# 16-Bit_Register.net
KiCad netlist of a schematic drawn in EAGLE
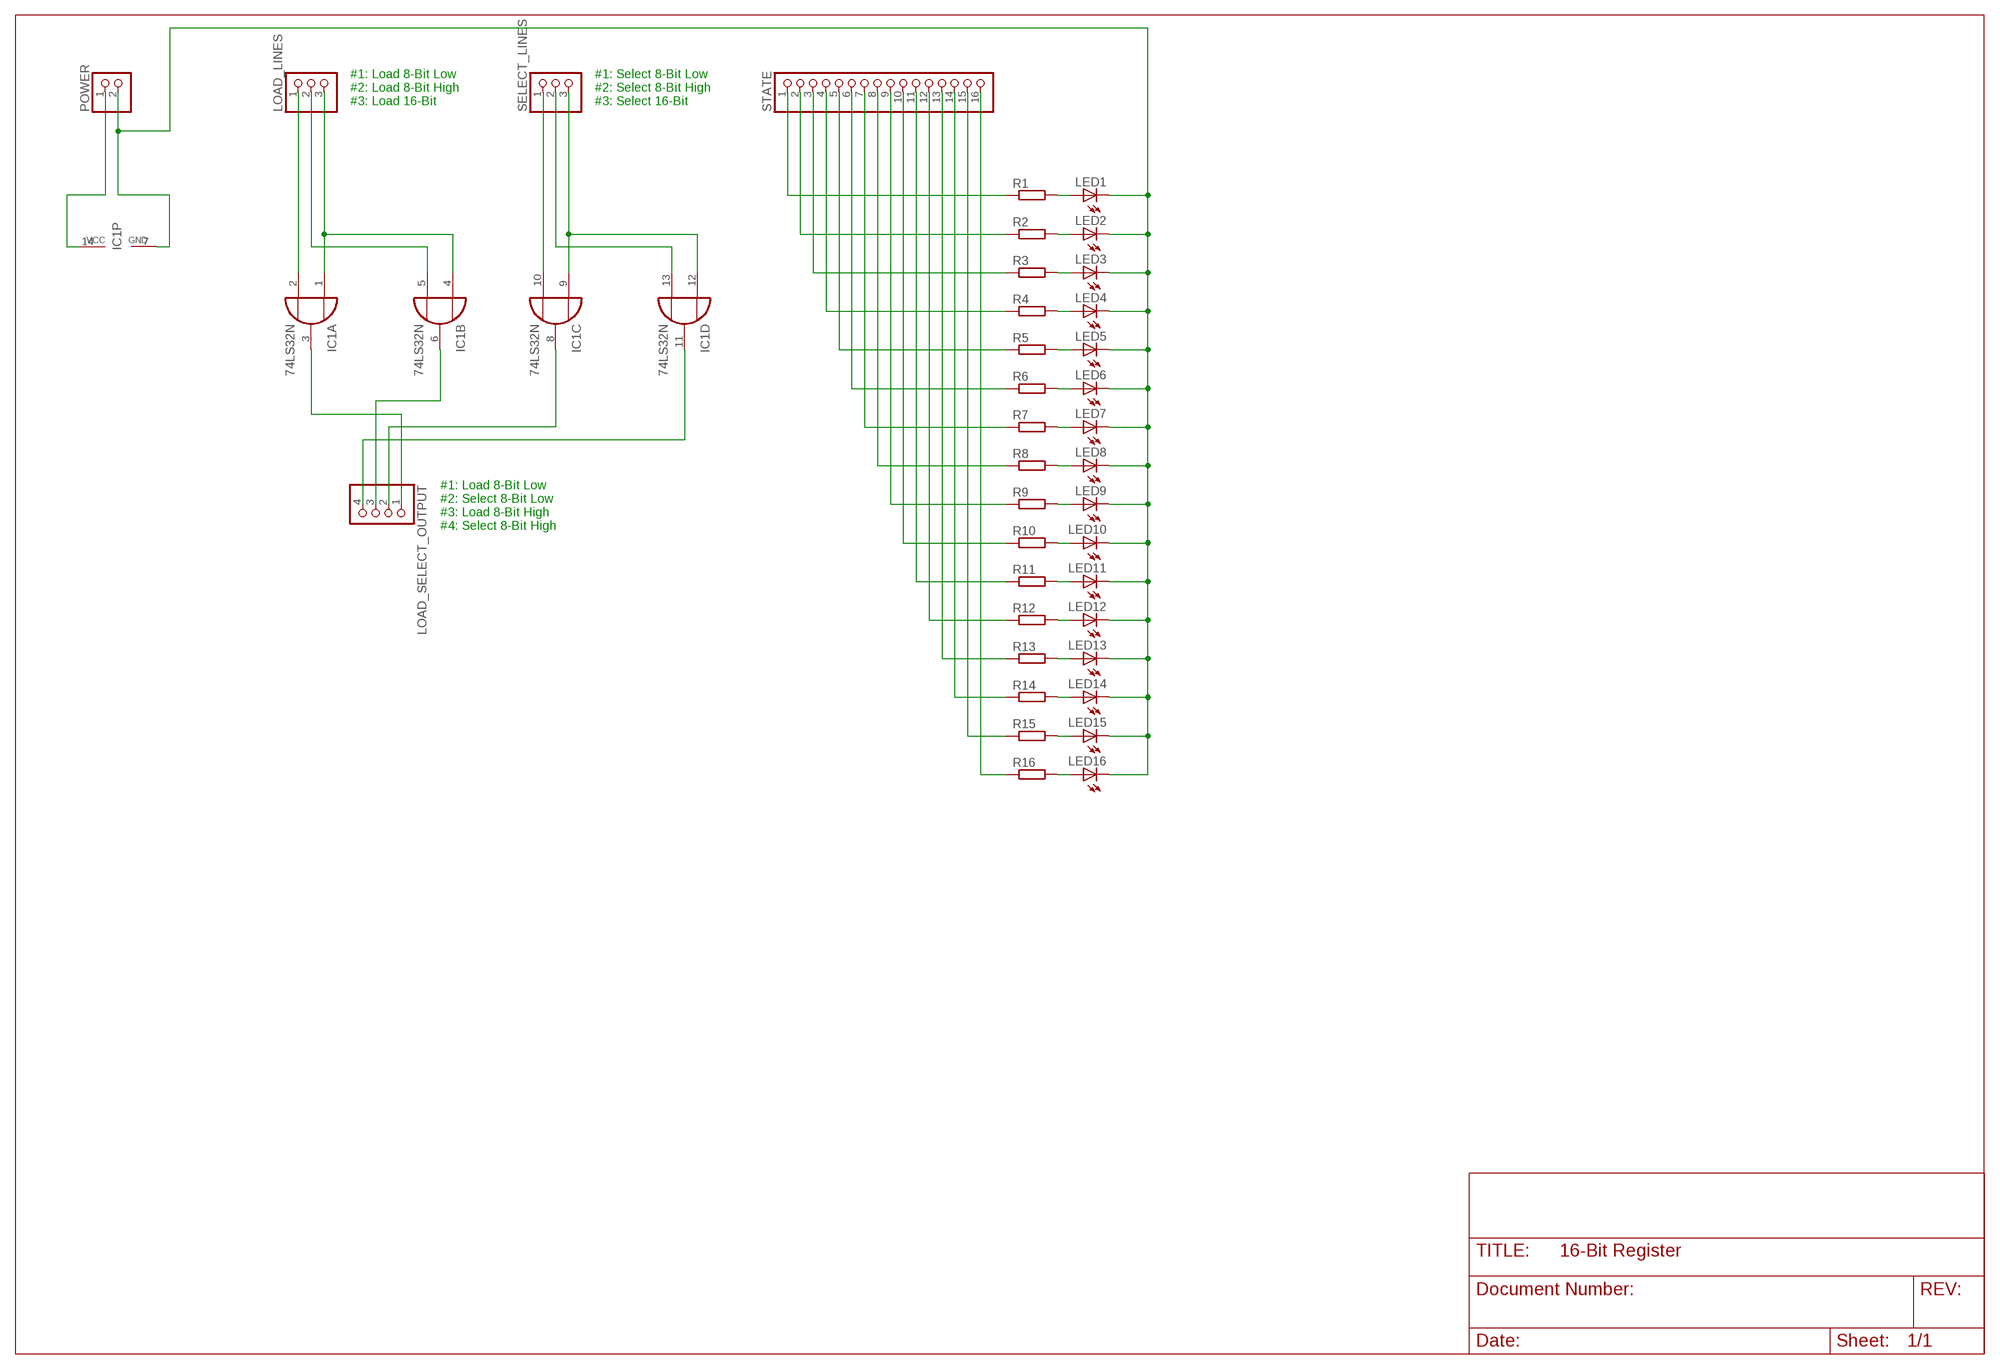
[diagram p0: schematic, sheet 1]

(export (version "E")
  (design (tool "Eeschema 10.0.6"))
  (components
    (comp (ref "IC1")
      (value "74LS32N")
      (footprint "eagle-import:DIL14")
      (libsource (lib "eagle-import") (part "7432NLS"))
    )
    (comp (ref "LED1")
      (value "LED3MM")
      (footprint "eagle-import:LED3MM")
      (libsource (lib "eagle-import") (part "LED3MM"))
    )
    (comp (ref "LED2")
      (value "LED3MM")
      (footprint "eagle-import:LED3MM")
      (libsource (lib "eagle-import") (part "LED3MM"))
    )
    (comp (ref "LED3")
      (value "LED3MM")
      (footprint "eagle-import:LED3MM")
      (libsource (lib "eagle-import") (part "LED3MM"))
    )
    (comp (ref "LED4")
      (value "LED3MM")
      (footprint "eagle-import:LED3MM")
      (libsource (lib "eagle-import") (part "LED3MM"))
    )
    (comp (ref "LED5")
      (value "LED3MM")
      (footprint "eagle-import:LED3MM")
      (libsource (lib "eagle-import") (part "LED3MM"))
    )
    (comp (ref "LED6")
      (value "LED3MM")
      (footprint "eagle-import:LED3MM")
      (libsource (lib "eagle-import") (part "LED3MM"))
    )
    (comp (ref "LED7")
      (value "LED3MM")
      (footprint "eagle-import:LED3MM")
      (libsource (lib "eagle-import") (part "LED3MM"))
    )
    (comp (ref "LED8")
      (value "LED3MM")
      (footprint "eagle-import:LED3MM")
      (libsource (lib "eagle-import") (part "LED3MM"))
    )
    (comp (ref "LED9")
      (value "LED3MM")
      (footprint "eagle-import:LED3MM")
      (libsource (lib "eagle-import") (part "LED3MM"))
    )
    (comp (ref "LED10")
      (value "LED3MM")
      (footprint "eagle-import:LED3MM")
      (libsource (lib "eagle-import") (part "LED3MM"))
    )
    (comp (ref "LED11")
      (value "LED3MM")
      (footprint "eagle-import:LED3MM")
      (libsource (lib "eagle-import") (part "LED3MM"))
    )
    (comp (ref "LED12")
      (value "LED3MM")
      (footprint "eagle-import:LED3MM")
      (libsource (lib "eagle-import") (part "LED3MM"))
    )
    (comp (ref "LED13")
      (value "LED3MM")
      (footprint "eagle-import:LED3MM")
      (libsource (lib "eagle-import") (part "LED3MM"))
    )
    (comp (ref "LED14")
      (value "LED3MM")
      (footprint "eagle-import:LED3MM")
      (libsource (lib "eagle-import") (part "LED3MM"))
    )
    (comp (ref "LED15")
      (value "LED3MM")
      (footprint "eagle-import:LED3MM")
      (libsource (lib "eagle-import") (part "LED3MM"))
    )
    (comp (ref "LED16")
      (value "LED3MM")
      (footprint "eagle-import:LED3MM")
      (libsource (lib "eagle-import") (part "LED3MM"))
    )
    (comp (ref "LOAD_LINES")
      (value "PINHD-1X3")
      (footprint "eagle-import:1X03")
      (libsource (lib "eagle-import") (part "PINHD-1X3"))
    )
    (comp (ref "LOAD_SELECT_OUTPUT")
      (value "PINHD-1X4")
      (footprint "eagle-import:1X04")
      (libsource (lib "eagle-import") (part "PINHD-1X4"))
    )
    (comp (ref "POWER")
      (value "PINHD-1X2")
      (footprint "eagle-import:1X02")
      (libsource (lib "eagle-import") (part "PINHD-1X2"))
    )
    (comp (ref "R1")
      (value "R-EU_0207/7")
      (footprint "eagle-import:0207_7")
      (libsource (lib "eagle-import") (part "R-EU_0207/7"))
    )
    (comp (ref "R2")
      (value "R-EU_0207/7")
      (footprint "eagle-import:0207_7")
      (libsource (lib "eagle-import") (part "R-EU_0207/7"))
    )
    (comp (ref "R3")
      (value "R-EU_0207/7")
      (footprint "eagle-import:0207_7")
      (libsource (lib "eagle-import") (part "R-EU_0207/7"))
    )
    (comp (ref "R4")
      (value "R-EU_0207/7")
      (footprint "eagle-import:0207_7")
      (libsource (lib "eagle-import") (part "R-EU_0207/7"))
    )
    (comp (ref "R5")
      (value "R-EU_0207/7")
      (footprint "eagle-import:0207_7")
      (libsource (lib "eagle-import") (part "R-EU_0207/7"))
    )
    (comp (ref "R6")
      (value "R-EU_0207/7")
      (footprint "eagle-import:0207_7")
      (libsource (lib "eagle-import") (part "R-EU_0207/7"))
    )
    (comp (ref "R7")
      (value "R-EU_0207/7")
      (footprint "eagle-import:0207_7")
      (libsource (lib "eagle-import") (part "R-EU_0207/7"))
    )
    (comp (ref "R8")
      (value "R-EU_0207/7")
      (footprint "eagle-import:0207_7")
      (libsource (lib "eagle-import") (part "R-EU_0207/7"))
    )
    (comp (ref "R9")
      (value "R-EU_0207/7")
      (footprint "eagle-import:0207_7")
      (libsource (lib "eagle-import") (part "R-EU_0207/7"))
    )
    (comp (ref "R10")
      (value "R-EU_0207/7")
      (footprint "eagle-import:0207_7")
      (libsource (lib "eagle-import") (part "R-EU_0207/7"))
    )
    (comp (ref "R11")
      (value "R-EU_0207/7")
      (footprint "eagle-import:0207_7")
      (libsource (lib "eagle-import") (part "R-EU_0207/7"))
    )
    (comp (ref "R12")
      (value "R-EU_0207/7")
      (footprint "eagle-import:0207_7")
      (libsource (lib "eagle-import") (part "R-EU_0207/7"))
    )
    (comp (ref "R13")
      (value "R-EU_0207/7")
      (footprint "eagle-import:0207_7")
      (libsource (lib "eagle-import") (part "R-EU_0207/7"))
    )
    (comp (ref "R14")
      (value "R-EU_0207/7")
      (footprint "eagle-import:0207_7")
      (libsource (lib "eagle-import") (part "R-EU_0207/7"))
    )
    (comp (ref "R15")
      (value "R-EU_0207/7")
      (footprint "eagle-import:0207_7")
      (libsource (lib "eagle-import") (part "R-EU_0207/7"))
    )
    (comp (ref "R16")
      (value "R-EU_0207/7")
      (footprint "eagle-import:0207_7")
      (libsource (lib "eagle-import") (part "R-EU_0207/7"))
    )
    (comp (ref "SELECT_LINES")
      (value "PINHD-1X3")
      (footprint "eagle-import:1X03")
      (libsource (lib "eagle-import") (part "PINHD-1X3"))
    )
    (comp (ref "STATE")
      (value "PINHD-1X16")
      (footprint "eagle-import:1X16")
      (libsource (lib "eagle-import") (part "PINHD-1X16"))
    )
  )
  (nets
    (net (code "1") (name "Net-(IC1A-I0)") (class "Default")
      (node (ref "IC1") (pin "1") (pinfunction "I0_1") (pintype "input"))
      (node (ref "IC1") (pin "4") (pinfunction "I0_4") (pintype "input"))
      (node (ref "LOAD_LINES") (pin "3") (pinfunction "3_3") (pintype "passive"))
    )
    (net (code "2") (name "Net-(IC1A-I1)") (class "Default")
      (node (ref "IC1") (pin "2") (pinfunction "I1_2") (pintype "input"))
      (node (ref "LOAD_LINES") (pin "1") (pinfunction "1_1") (pintype "passive"))
    )
    (net (code "3") (name "Net-(IC1A-O)") (class "Default")
      (node (ref "IC1") (pin "3") (pinfunction "O_3") (pintype "output"))
      (node (ref "LOAD_SELECT_OUTPUT") (pin "1") (pinfunction "1_1") (pintype "passive"))
    )
    (net (code "4") (name "Net-(IC1B-I1)") (class "Default")
      (node (ref "IC1") (pin "5") (pinfunction "I1_5") (pintype "input"))
      (node (ref "LOAD_LINES") (pin "2") (pinfunction "2_2") (pintype "passive"))
    )
    (net (code "5") (name "Net-(IC1B-O)") (class "Default")
      (node (ref "IC1") (pin "6") (pinfunction "O_6") (pintype "output"))
      (node (ref "LOAD_SELECT_OUTPUT") (pin "3") (pinfunction "3_3") (pintype "passive"))
    )
    (net (code "6") (name "Net-(IC1C-I0)") (class "Default")
      (node (ref "IC1") (pin "12") (pinfunction "I0_12") (pintype "input"))
      (node (ref "IC1") (pin "9") (pinfunction "I0_9") (pintype "input"))
      (node (ref "SELECT_LINES") (pin "3") (pinfunction "3_3") (pintype "passive"))
    )
    (net (code "7") (name "Net-(IC1C-I1)") (class "Default")
      (node (ref "IC1") (pin "10") (pinfunction "I1_10") (pintype "input"))
      (node (ref "SELECT_LINES") (pin "1") (pinfunction "1_1") (pintype "passive"))
    )
    (net (code "8") (name "Net-(IC1C-O)") (class "Default")
      (node (ref "IC1") (pin "8") (pinfunction "O_8") (pintype "output"))
      (node (ref "LOAD_SELECT_OUTPUT") (pin "2") (pinfunction "2_2") (pintype "passive"))
    )
    (net (code "9") (name "Net-(IC1D-I1)") (class "Default")
      (node (ref "IC1") (pin "13") (pinfunction "I1_13") (pintype "input"))
      (node (ref "SELECT_LINES") (pin "2") (pinfunction "2_2") (pintype "passive"))
    )
    (net (code "10") (name "Net-(IC1D-O)") (class "Default")
      (node (ref "IC1") (pin "11") (pinfunction "O_11") (pintype "output"))
      (node (ref "LOAD_SELECT_OUTPUT") (pin "4") (pinfunction "4_4") (pintype "passive"))
    )
    (net (code "11") (name "Net-(IC1E-GND)") (class "Default")
      (node (ref "IC1") (pin "7") (pinfunction "GND_7") (pintype "power_in"))
      (node (ref "LED1") (pin "K") (pinfunction "C_K") (pintype "passive"))
      (node (ref "LED10") (pin "K") (pinfunction "C_K") (pintype "passive"))
      (node (ref "LED11") (pin "K") (pinfunction "C_K") (pintype "passive"))
      (node (ref "LED12") (pin "K") (pinfunction "C_K") (pintype "passive"))
      (node (ref "LED13") (pin "K") (pinfunction "C_K") (pintype "passive"))
      (node (ref "LED14") (pin "K") (pinfunction "C_K") (pintype "passive"))
      (node (ref "LED15") (pin "K") (pinfunction "C_K") (pintype "passive"))
      (node (ref "LED16") (pin "K") (pinfunction "C_K") (pintype "passive"))
      (node (ref "LED2") (pin "K") (pinfunction "C_K") (pintype "passive"))
      (node (ref "LED3") (pin "K") (pinfunction "C_K") (pintype "passive"))
      (node (ref "LED4") (pin "K") (pinfunction "C_K") (pintype "passive"))
      (node (ref "LED5") (pin "K") (pinfunction "C_K") (pintype "passive"))
      (node (ref "LED6") (pin "K") (pinfunction "C_K") (pintype "passive"))
      (node (ref "LED7") (pin "K") (pinfunction "C_K") (pintype "passive"))
      (node (ref "LED8") (pin "K") (pinfunction "C_K") (pintype "passive"))
      (node (ref "LED9") (pin "K") (pinfunction "C_K") (pintype "passive"))
      (node (ref "POWER") (pin "2") (pinfunction "2_2") (pintype "passive"))
    )
    (net (code "12") (name "Net-(IC1E-VCC)") (class "Default")
      (node (ref "IC1") (pin "14") (pinfunction "VCC_14") (pintype "power_in"))
      (node (ref "POWER") (pin "1") (pinfunction "1_1") (pintype "passive"))
    )
    (net (code "13") (name "Net-(LED1-PadA)") (class "Default")
      (node (ref "LED1") (pin "A") (pinfunction "A_A") (pintype "passive"))
      (node (ref "R1") (pin "2") (pinfunction "2_2") (pintype "passive"))
    )
    (net (code "14") (name "Net-(LED2-PadA)") (class "Default")
      (node (ref "LED2") (pin "A") (pinfunction "A_A") (pintype "passive"))
      (node (ref "R2") (pin "2") (pinfunction "2_2") (pintype "passive"))
    )
    (net (code "15") (name "Net-(LED3-PadA)") (class "Default")
      (node (ref "LED3") (pin "A") (pinfunction "A_A") (pintype "passive"))
      (node (ref "R3") (pin "2") (pinfunction "2_2") (pintype "passive"))
    )
    (net (code "16") (name "Net-(LED4-PadA)") (class "Default")
      (node (ref "LED4") (pin "A") (pinfunction "A_A") (pintype "passive"))
      (node (ref "R4") (pin "2") (pinfunction "2_2") (pintype "passive"))
    )
    (net (code "17") (name "Net-(LED5-PadA)") (class "Default")
      (node (ref "LED5") (pin "A") (pinfunction "A_A") (pintype "passive"))
      (node (ref "R5") (pin "2") (pinfunction "2_2") (pintype "passive"))
    )
    (net (code "18") (name "Net-(LED6-PadA)") (class "Default")
      (node (ref "LED6") (pin "A") (pinfunction "A_A") (pintype "passive"))
      (node (ref "R6") (pin "2") (pinfunction "2_2") (pintype "passive"))
    )
    (net (code "19") (name "Net-(LED7-PadA)") (class "Default")
      (node (ref "LED7") (pin "A") (pinfunction "A_A") (pintype "passive"))
      (node (ref "R7") (pin "2") (pinfunction "2_2") (pintype "passive"))
    )
    (net (code "20") (name "Net-(LED8-PadA)") (class "Default")
      (node (ref "LED8") (pin "A") (pinfunction "A_A") (pintype "passive"))
      (node (ref "R8") (pin "2") (pinfunction "2_2") (pintype "passive"))
    )
    (net (code "21") (name "Net-(LED9-PadA)") (class "Default")
      (node (ref "LED9") (pin "A") (pinfunction "A_A") (pintype "passive"))
      (node (ref "R9") (pin "2") (pinfunction "2_2") (pintype "passive"))
    )
    (net (code "22") (name "Net-(LED10-PadA)") (class "Default")
      (node (ref "LED10") (pin "A") (pinfunction "A_A") (pintype "passive"))
      (node (ref "R10") (pin "2") (pinfunction "2_2") (pintype "passive"))
    )
    (net (code "23") (name "Net-(LED11-PadA)") (class "Default")
      (node (ref "LED11") (pin "A") (pinfunction "A_A") (pintype "passive"))
      (node (ref "R11") (pin "2") (pinfunction "2_2") (pintype "passive"))
    )
    (net (code "24") (name "Net-(LED12-PadA)") (class "Default")
      (node (ref "LED12") (pin "A") (pinfunction "A_A") (pintype "passive"))
      (node (ref "R12") (pin "2") (pinfunction "2_2") (pintype "passive"))
    )
    (net (code "25") (name "Net-(LED13-PadA)") (class "Default")
      (node (ref "LED13") (pin "A") (pinfunction "A_A") (pintype "passive"))
      (node (ref "R13") (pin "2") (pinfunction "2_2") (pintype "passive"))
    )
    (net (code "26") (name "Net-(LED14-PadA)") (class "Default")
      (node (ref "LED14") (pin "A") (pinfunction "A_A") (pintype "passive"))
      (node (ref "R14") (pin "2") (pinfunction "2_2") (pintype "passive"))
    )
    (net (code "27") (name "Net-(LED15-PadA)") (class "Default")
      (node (ref "LED15") (pin "A") (pinfunction "A_A") (pintype "passive"))
      (node (ref "R15") (pin "2") (pinfunction "2_2") (pintype "passive"))
    )
    (net (code "28") (name "Net-(LED16-PadA)") (class "Default")
      (node (ref "LED16") (pin "A") (pinfunction "A_A") (pintype "passive"))
      (node (ref "R16") (pin "2") (pinfunction "2_2") (pintype "passive"))
    )
    (net (code "29") (name "Net-(R1-Pad1)") (class "Default")
      (node (ref "R1") (pin "1") (pinfunction "1_1") (pintype "passive"))
      (node (ref "STATE") (pin "1") (pinfunction "1_1") (pintype "passive"))
    )
    (net (code "30") (name "Net-(R2-Pad1)") (class "Default")
      (node (ref "R2") (pin "1") (pinfunction "1_1") (pintype "passive"))
      (node (ref "STATE") (pin "2") (pinfunction "2_2") (pintype "passive"))
    )
    (net (code "31") (name "Net-(R3-Pad1)") (class "Default")
      (node (ref "R3") (pin "1") (pinfunction "1_1") (pintype "passive"))
      (node (ref "STATE") (pin "3") (pinfunction "3_3") (pintype "passive"))
    )
    (net (code "32") (name "Net-(R4-Pad1)") (class "Default")
      (node (ref "R4") (pin "1") (pinfunction "1_1") (pintype "passive"))
      (node (ref "STATE") (pin "4") (pinfunction "4_4") (pintype "passive"))
    )
    (net (code "33") (name "Net-(R5-Pad1)") (class "Default")
      (node (ref "R5") (pin "1") (pinfunction "1_1") (pintype "passive"))
      (node (ref "STATE") (pin "5") (pinfunction "5_5") (pintype "passive"))
    )
    (net (code "34") (name "Net-(R6-Pad1)") (class "Default")
      (node (ref "R6") (pin "1") (pinfunction "1_1") (pintype "passive"))
      (node (ref "STATE") (pin "6") (pinfunction "6_6") (pintype "passive"))
    )
    (net (code "35") (name "Net-(R7-Pad1)") (class "Default")
      (node (ref "R7") (pin "1") (pinfunction "1_1") (pintype "passive"))
      (node (ref "STATE") (pin "7") (pinfunction "7_7") (pintype "passive"))
    )
    (net (code "36") (name "Net-(R8-Pad1)") (class "Default")
      (node (ref "R8") (pin "1") (pinfunction "1_1") (pintype "passive"))
      (node (ref "STATE") (pin "8") (pinfunction "8_8") (pintype "passive"))
    )
    (net (code "37") (name "Net-(R9-Pad1)") (class "Default")
      (node (ref "R9") (pin "1") (pinfunction "1_1") (pintype "passive"))
      (node (ref "STATE") (pin "9") (pinfunction "9_9") (pintype "passive"))
    )
    (net (code "38") (name "Net-(R10-Pad1)") (class "Default")
      (node (ref "R10") (pin "1") (pinfunction "1_1") (pintype "passive"))
      (node (ref "STATE") (pin "10") (pinfunction "10_10") (pintype "passive"))
    )
    (net (code "39") (name "Net-(R11-Pad1)") (class "Default")
      (node (ref "R11") (pin "1") (pinfunction "1_1") (pintype "passive"))
      (node (ref "STATE") (pin "11") (pinfunction "11_11") (pintype "passive"))
    )
    (net (code "40") (name "Net-(R12-Pad1)") (class "Default")
      (node (ref "R12") (pin "1") (pinfunction "1_1") (pintype "passive"))
      (node (ref "STATE") (pin "12") (pinfunction "12_12") (pintype "passive"))
    )
    (net (code "41") (name "Net-(R13-Pad1)") (class "Default")
      (node (ref "R13") (pin "1") (pinfunction "1_1") (pintype "passive"))
      (node (ref "STATE") (pin "13") (pinfunction "13_13") (pintype "passive"))
    )
    (net (code "42") (name "Net-(R14-Pad1)") (class "Default")
      (node (ref "R14") (pin "1") (pinfunction "1_1") (pintype "passive"))
      (node (ref "STATE") (pin "14") (pinfunction "14_14") (pintype "passive"))
    )
    (net (code "43") (name "Net-(R15-Pad1)") (class "Default")
      (node (ref "R15") (pin "1") (pinfunction "1_1") (pintype "passive"))
      (node (ref "STATE") (pin "15") (pinfunction "15_15") (pintype "passive"))
    )
    (net (code "44") (name "Net-(R16-Pad1)") (class "Default")
      (node (ref "R16") (pin "1") (pinfunction "1_1") (pintype "passive"))
      (node (ref "STATE") (pin "16") (pinfunction "16_16") (pintype "passive"))
    )
  )
)
